# 4KB_SRAM_Module_SCH_ALTIUM.net
KiCad netlist of a schematic drawn in Altium Designer
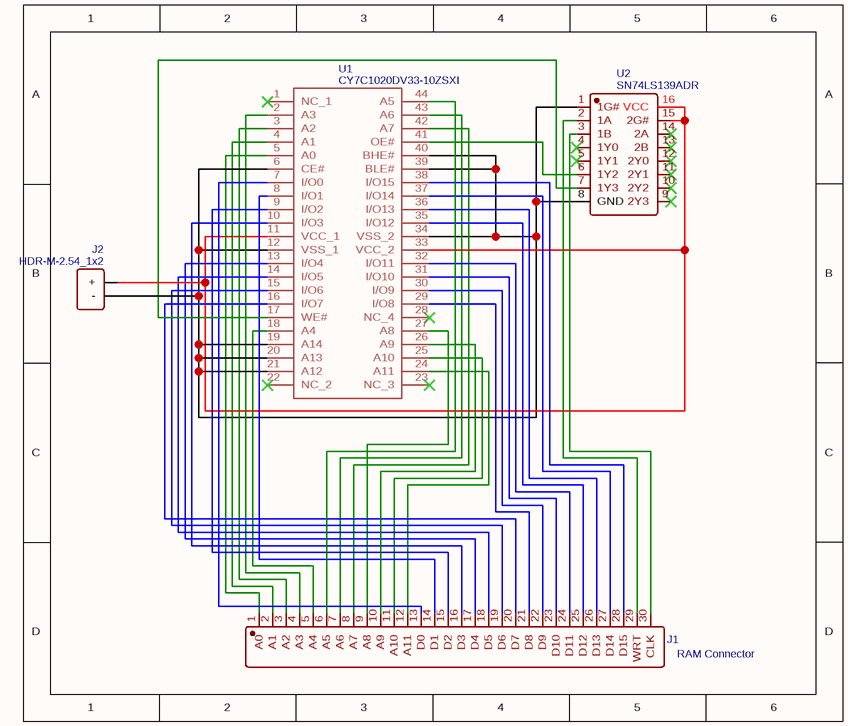
[diagram p0: 4KB_SRAM_Module_SCH_ALTIUM.schdoc]

(export (version "E")
  (design (tool "Eeschema 10.0.6"))
  (components
    (comp (ref "J1") (value "RAM Connector") (libsource (lib "altium-import") (part "root_1_RAM Connector_")))
    (comp (ref "J2")
      (value "HDR-M-2.54_1x2")
      (fields (field (name "BOM_SUPPLIER PART") "C124375") (field (name "CONTRIBUTOR") "LCEDA_Lib"))
      (libsource (lib "altium-import") (part "root_0_HDR-M-2.54_1x2_"))
    )
    (comp (ref "U1")
      (value "CY7C1020DV33-10ZSXI")
      (fields (field (name "CONTRIBUTOR") "shawleonm"))
      (libsource (lib "altium-import") (part "root_0_CY7C1020DV33-10ZSXI_"))
    )
    (comp (ref "U2")
      (value "SN74LS139ADR")
      (fields (field (name "BOM_SUPPLIER PART") "C7738") (field (name "CONTRIBUTOR") "LCSC"))
      (libsource (lib "altium-import") (part "root_0_SN74LS139ADR_"))
    )
  )
  (nets
    (net (code "1") (name "Net-(J1-A0)") (class "Default")
      (node (ref "J1") (pin "1") (pinfunction "A0_1") (pintype "passive"))
      (node (ref "U1") (pin "5") (pinfunction "A0_5") (pintype "passive"))
    )
    (net (code "2") (name "Net-(J1-A1)") (class "Default")
      (node (ref "J1") (pin "2") (pinfunction "A1_2") (pintype "passive"))
      (node (ref "U1") (pin "4") (pinfunction "A1_4") (pintype "passive"))
    )
    (net (code "3") (name "Net-(J1-A2)") (class "Default")
      (node (ref "J1") (pin "3") (pinfunction "A2_3") (pintype "passive"))
      (node (ref "U1") (pin "3") (pinfunction "A2_3") (pintype "passive"))
    )
    (net (code "4") (name "Net-(J1-A3)") (class "Default")
      (node (ref "J1") (pin "4") (pinfunction "A3_4") (pintype "passive"))
      (node (ref "U1") (pin "2") (pinfunction "A3_2") (pintype "passive"))
    )
    (net (code "5") (name "Net-(J1-A4)") (class "Default")
      (node (ref "J1") (pin "5") (pinfunction "A4_5") (pintype "passive"))
      (node (ref "U1") (pin "18") (pinfunction "A4_18") (pintype "passive"))
    )
    (net (code "6") (name "Net-(J1-A5)") (class "Default")
      (node (ref "J1") (pin "6") (pinfunction "A5_6") (pintype "passive"))
      (node (ref "U1") (pin "44") (pinfunction "A5_44") (pintype "passive"))
    )
    (net (code "7") (name "Net-(J1-A6)") (class "Default")
      (node (ref "J1") (pin "7") (pinfunction "A6_7") (pintype "passive"))
      (node (ref "U1") (pin "43") (pinfunction "A6_43") (pintype "passive"))
    )
    (net (code "8") (name "Net-(J1-A7)") (class "Default")
      (node (ref "J1") (pin "8") (pinfunction "A7_8") (pintype "passive"))
      (node (ref "U1") (pin "42") (pinfunction "A7_42") (pintype "passive"))
    )
    (net (code "9") (name "Net-(J1-A8)") (class "Default")
      (node (ref "J1") (pin "9") (pinfunction "A8_9") (pintype "passive"))
      (node (ref "U1") (pin "27") (pinfunction "A8_27") (pintype "passive"))
    )
    (net (code "10") (name "Net-(J1-A9)") (class "Default")
      (node (ref "J1") (pin "10") (pinfunction "A9_10") (pintype "passive"))
      (node (ref "U1") (pin "26") (pinfunction "A9_26") (pintype "passive"))
    )
    (net (code "11") (name "Net-(J1-A10)") (class "Default")
      (node (ref "J1") (pin "11") (pinfunction "A10_11") (pintype "passive"))
      (node (ref "U1") (pin "25") (pinfunction "A10_25") (pintype "passive"))
    )
    (net (code "12") (name "Net-(J1-A11)") (class "Default")
      (node (ref "J1") (pin "12") (pinfunction "A11_12") (pintype "passive"))
      (node (ref "U1") (pin "24") (pinfunction "A11_24") (pintype "passive"))
    )
    (net (code "13") (name "Net-(J1-CLK)") (class "Default")
      (node (ref "J1") (pin "30") (pinfunction "CLK_30") (pintype "passive"))
      (node (ref "U2") (pin "3") (pinfunction "1B_3") (pintype "passive"))
    )
    (net (code "14") (name "Net-(J1-D0)") (class "Default")
      (node (ref "J1") (pin "13") (pinfunction "D0_13") (pintype "passive"))
      (node (ref "U1") (pin "7") (pinfunction "I/O0_7") (pintype "passive"))
    )
    (net (code "15") (name "Net-(J1-D1)") (class "Default")
      (node (ref "J1") (pin "14") (pinfunction "D1_14") (pintype "passive"))
      (node (ref "U1") (pin "8") (pinfunction "I/O1_8") (pintype "passive"))
    )
    (net (code "16") (name "Net-(J1-D2)") (class "Default")
      (node (ref "J1") (pin "15") (pinfunction "D2_15") (pintype "passive"))
      (node (ref "U1") (pin "9") (pinfunction "I/O2_9") (pintype "passive"))
    )
    (net (code "17") (name "Net-(J1-D3)") (class "Default")
      (node (ref "J1") (pin "16") (pinfunction "D3_16") (pintype "passive"))
      (node (ref "U1") (pin "10") (pinfunction "I/O3_10") (pintype "passive"))
    )
    (net (code "18") (name "Net-(J1-D4)") (class "Default")
      (node (ref "J1") (pin "17") (pinfunction "D4_17") (pintype "passive"))
      (node (ref "U1") (pin "13") (pinfunction "I/O4_13") (pintype "passive"))
    )
    (net (code "19") (name "Net-(J1-D5)") (class "Default")
      (node (ref "J1") (pin "18") (pinfunction "D5_18") (pintype "passive"))
      (node (ref "U1") (pin "14") (pinfunction "I/O5_14") (pintype "passive"))
    )
    (net (code "20") (name "Net-(J1-D6)") (class "Default")
      (node (ref "J1") (pin "19") (pinfunction "D6_19") (pintype "passive"))
      (node (ref "U1") (pin "15") (pinfunction "I/O6_15") (pintype "passive"))
    )
    (net (code "21") (name "Net-(J1-D7)") (class "Default")
      (node (ref "J1") (pin "20") (pinfunction "D7_20") (pintype "passive"))
      (node (ref "U1") (pin "16") (pinfunction "I/O7_16") (pintype "passive"))
    )
    (net (code "22") (name "Net-(J1-D8)") (class "Default")
      (node (ref "J1") (pin "21") (pinfunction "D8_21") (pintype "passive"))
      (node (ref "U1") (pin "29") (pinfunction "I/O8_29") (pintype "passive"))
    )
    (net (code "23") (name "Net-(J1-D9)") (class "Default")
      (node (ref "J1") (pin "22") (pinfunction "D9_22") (pintype "passive"))
      (node (ref "U1") (pin "30") (pinfunction "I/O9_30") (pintype "passive"))
    )
    (net (code "24") (name "Net-(J1-D10)") (class "Default")
      (node (ref "J1") (pin "23") (pinfunction "D10_23") (pintype "passive"))
      (node (ref "U1") (pin "31") (pinfunction "I/O10_31") (pintype "passive"))
    )
    (net (code "25") (name "Net-(J1-D11)") (class "Default")
      (node (ref "J1") (pin "24") (pinfunction "D11_24") (pintype "passive"))
      (node (ref "U1") (pin "32") (pinfunction "I/O11_32") (pintype "passive"))
    )
    (net (code "26") (name "Net-(J1-D12)") (class "Default")
      (node (ref "J1") (pin "25") (pinfunction "D12_25") (pintype "passive"))
      (node (ref "U1") (pin "35") (pinfunction "I/O12_35") (pintype "passive"))
    )
    (net (code "27") (name "Net-(J1-D13)") (class "Default")
      (node (ref "J1") (pin "26") (pinfunction "D13_26") (pintype "passive"))
      (node (ref "U1") (pin "36") (pinfunction "I/O13_36") (pintype "passive"))
    )
    (net (code "28") (name "Net-(J1-D14)") (class "Default")
      (node (ref "J1") (pin "27") (pinfunction "D14_27") (pintype "passive"))
      (node (ref "U1") (pin "37") (pinfunction "I/O14_37") (pintype "passive"))
    )
    (net (code "29") (name "Net-(J1-D15)") (class "Default")
      (node (ref "J1") (pin "28") (pinfunction "D15_28") (pintype "passive"))
      (node (ref "U1") (pin "38") (pinfunction "I/O15_38") (pintype "passive"))
    )
    (net (code "30") (name "Net-(J1-WRT)") (class "Default")
      (node (ref "J1") (pin "29") (pinfunction "WRT_29") (pintype "passive"))
      (node (ref "U2") (pin "2") (pinfunction "1A_2") (pintype "passive"))
    )
    (net (code "31") (name "Net-(J2-+)") (class "Default")
      (node (ref "J2") (pin "1") (pinfunction "+_1") (pintype "passive"))
      (node (ref "U1") (pin "11") (pinfunction "VCC_1_11") (pintype "passive"))
      (node (ref "U1") (pin "33") (pinfunction "VCC_2_33") (pintype "passive"))
      (node (ref "U2") (pin "15") (pinfunction "2G#_15") (pintype "passive"))
      (node (ref "U2") (pin "16") (pinfunction "VCC_16") (pintype "passive"))
    )
    (net (code "32") (name "Net-(J2--)") (class "Default")
      (node (ref "J2") (pin "2") (pinfunction "-_2") (pintype "passive"))
      (node (ref "U1") (pin "12") (pinfunction "VSS_1_12") (pintype "passive"))
      (node (ref "U1") (pin "19") (pinfunction "A14_19") (pintype "passive"))
      (node (ref "U1") (pin "20") (pinfunction "A13_20") (pintype "passive"))
      (node (ref "U1") (pin "21") (pinfunction "A12_21") (pintype "passive"))
      (node (ref "U1") (pin "34") (pinfunction "VSS_2_34") (pintype "passive"))
      (node (ref "U1") (pin "39") (pinfunction "BLE#_39") (pintype "passive"))
      (node (ref "U1") (pin "40") (pinfunction "BHE#_40") (pintype "passive"))
      (node (ref "U1") (pin "6") (pinfunction "CE#_6") (pintype "passive"))
      (node (ref "U2") (pin "1") (pinfunction "1G#_1") (pintype "passive"))
      (node (ref "U2") (pin "8") (pinfunction "GND_8") (pintype "passive"))
    )
    (net (code "33") (name "Net-(U1-OE#)") (class "Default")
      (node (ref "U1") (pin "41") (pinfunction "OE#_41") (pintype "passive"))
      (node (ref "U2") (pin "6") (pinfunction "1Y2_6") (pintype "passive"))
    )
    (net (code "34") (name "Net-(U1-WE#)") (class "Default")
      (node (ref "U1") (pin "17") (pinfunction "WE#_17") (pintype "passive"))
      (node (ref "U2") (pin "7") (pinfunction "1Y3_7") (pintype "passive"))
    )
    (net (code "35") (name "unconnected-(U1-NC_1-Pad1)") (class "Default")
      (node (ref "U1") (pin "1") (pinfunction "NC_1_1") (pintype "passive+no_connect"))
    )
    (net (code "36") (name "unconnected-(U1-NC_2-Pad22)") (class "Default")
      (node (ref "U1") (pin "22") (pinfunction "NC_2_22") (pintype "passive+no_connect"))
    )
    (net (code "37") (name "unconnected-(U1-NC_3-Pad23)") (class "Default")
      (node (ref "U1") (pin "23") (pinfunction "NC_3_23") (pintype "passive+no_connect"))
    )
    (net (code "38") (name "unconnected-(U1-NC_4-Pad28)") (class "Default")
      (node (ref "U1") (pin "28") (pinfunction "NC_4_28") (pintype "passive+no_connect"))
    )
    (net (code "39") (name "unconnected-(U2-1Y0-Pad4)") (class "Default")
      (node (ref "U2") (pin "4") (pinfunction "1Y0_4") (pintype "passive+no_connect"))
    )
    (net (code "40") (name "unconnected-(U2-1Y1-Pad5)") (class "Default")
      (node (ref "U2") (pin "5") (pinfunction "1Y1_5") (pintype "passive+no_connect"))
    )
    (net (code "41") (name "unconnected-(U2-2A-Pad14)") (class "Default")
      (node (ref "U2") (pin "14") (pinfunction "2A_14") (pintype "passive+no_connect"))
    )
    (net (code "42") (name "unconnected-(U2-2B-Pad13)") (class "Default")
      (node (ref "U2") (pin "13") (pinfunction "2B_13") (pintype "passive+no_connect"))
    )
    (net (code "43") (name "unconnected-(U2-2Y0-Pad12)") (class "Default")
      (node (ref "U2") (pin "12") (pinfunction "2Y0_12") (pintype "passive+no_connect"))
    )
    (net (code "44") (name "unconnected-(U2-2Y1-Pad11)") (class "Default")
      (node (ref "U2") (pin "11") (pinfunction "2Y1_11") (pintype "passive+no_connect"))
    )
    (net (code "45") (name "unconnected-(U2-2Y2-Pad10)") (class "Default")
      (node (ref "U2") (pin "10") (pinfunction "2Y2_10") (pintype "passive+no_connect"))
    )
    (net (code "46") (name "unconnected-(U2-2Y3-Pad9)") (class "Default")
      (node (ref "U2") (pin "9") (pinfunction "2Y3_9") (pintype "passive+no_connect"))
    )
  )
)
